# STM32-ROMI_Rev_A_4_3V_5V.net
KiCad netlist of a schematic drawn in Altium Designer
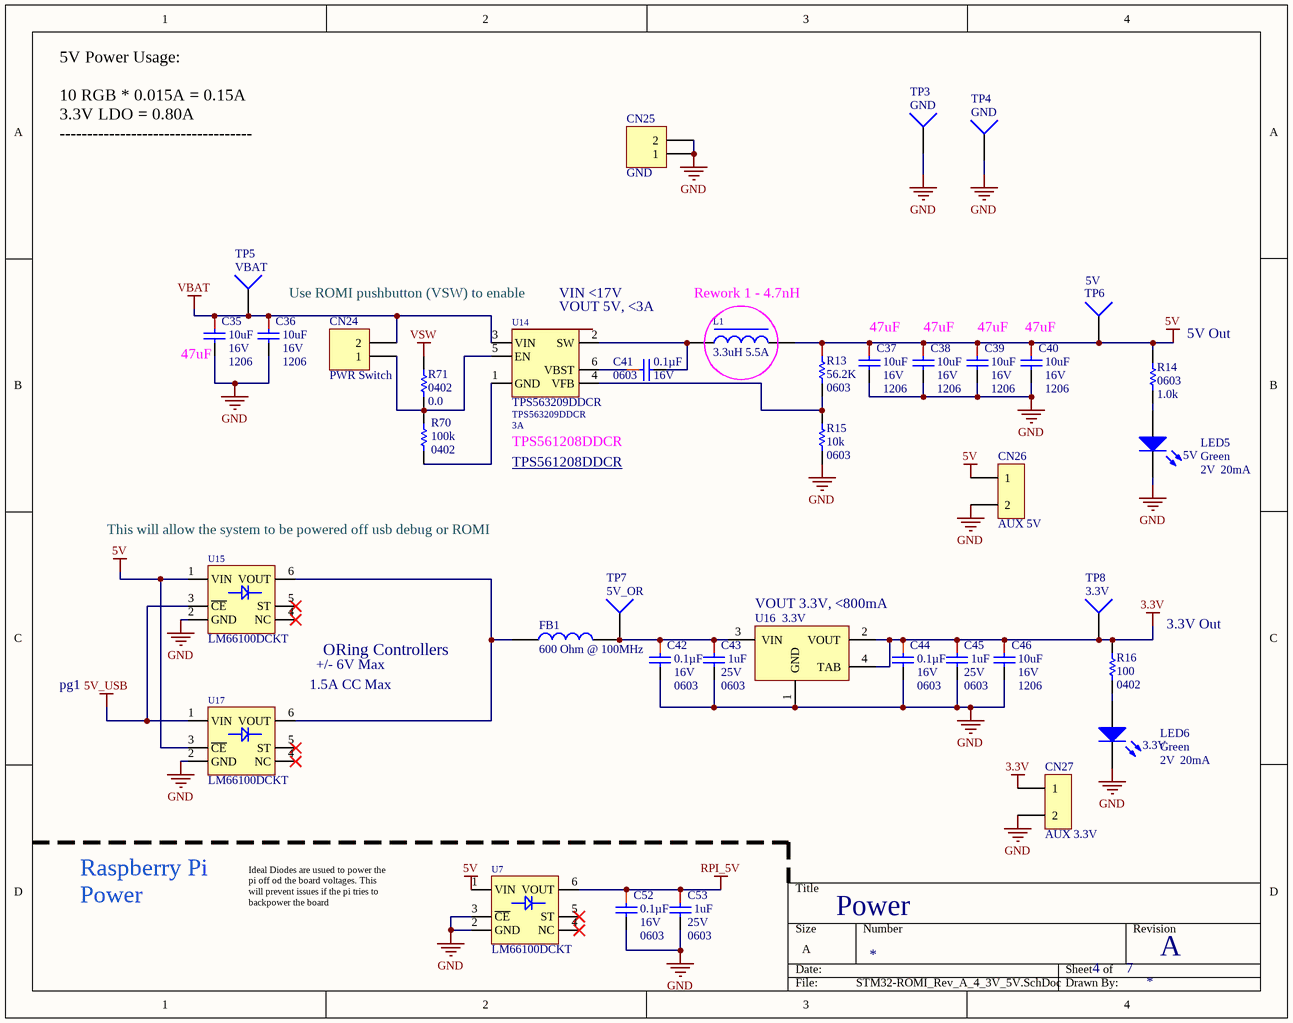
[diagram p0: STM32-ROMI_Rev_A_4_3V_5V.SchDoc]

(export (version "E")
  (design (tool "Eeschema 10.0.6"))
  (components
    (comp (ref "C35")
      (value "10uF")
      (footprint "CAPC1206(3216)_M")
      (fields (field (name "VOLTAGE - RATED") "16V") (field (name "PACKAGE") "1206"))
      (libsource (lib "Kyle-Passive") (part "CAP CER 10UF 16V 1206"))
    )
    (comp (ref "C36")
      (value "10uF")
      (footprint "CAPC1206(3216)_M")
      (fields (field (name "VOLTAGE - RATED") "16V") (field (name "PACKAGE") "1206"))
      (libsource (lib "Kyle-Passive") (part "CAP CER 10UF 16V 1206"))
    )
    (comp (ref "C37")
      (value "10uF")
      (footprint "CAPC1206(3216)_M")
      (fields (field (name "VOLTAGE - RATED") "16V") (field (name "PACKAGE") "1206"))
      (libsource (lib "Kyle-Passive") (part "CAP CER 10UF 16V 1206"))
    )
    (comp (ref "C38")
      (value "10uF")
      (footprint "CAPC1206(3216)_M")
      (fields (field (name "VOLTAGE - RATED") "16V") (field (name "PACKAGE") "1206"))
      (libsource (lib "Kyle-Passive") (part "CAP CER 10UF 16V 1206"))
    )
    (comp (ref "C39")
      (value "10uF")
      (footprint "CAPC1206(3216)_M")
      (fields (field (name "VOLTAGE - RATED") "16V") (field (name "PACKAGE") "1206"))
      (libsource (lib "Kyle-Passive") (part "CAP CER 10UF 16V 1206"))
    )
    (comp (ref "C40")
      (value "10uF")
      (footprint "CAPC1206(3216)_M")
      (fields (field (name "VOLTAGE - RATED") "16V") (field (name "PACKAGE") "1206"))
      (libsource (lib "Kyle-Passive") (part "CAP CER 10UF 16V 1206"))
    )
    (comp (ref "C41")
      (value "0.1uF")
      (footprint "CAPC0603(1608)_L")
      (description "0.1uF 0603 16V")
      (fields
        (field (name "MANUFACTURER") "Kemet")
        (field (name "MANUFACTURER PART NUMBER") "C0603C104K4RACTU")
        (field (name "CAPACITANCE") "0.1µF")
        (field (name "PACKAGE / CASE") "0603")
        (field (name "VOLTAGE - RATED") "16V")
      )
      (libsource (lib "Kyle-Passive") (part "CAP CER 0.1UF 16V 10% X7R 0603"))
    )
    (comp (ref "C42")
      (value "0.1uF")
      (footprint "CAPC0603(1608)_L")
      (description "0.1uF 0603 16V")
      (fields
        (field (name "MANUFACTURER") "Kemet")
        (field (name "MANUFACTURER PART NUMBER") "C0603C104K4RACTU")
        (field (name "CAPACITANCE") "0.1µF")
        (field (name "PACKAGE / CASE") "0603")
        (field (name "VOLTAGE - RATED") "16V")
      )
      (libsource (lib "Kyle-Passive") (part "CAP CER 0.1UF 16V 10% X7R 0603"))
    )
    (comp (ref "C43")
      (value "1uF")
      (footprint "CAPC0603(1608)_N")
      (description "1uF 0603 25V")
      (fields
        (field (name "MANUFACTURER") "TDK Corporation")
        (field (name "MANUFACTURER PART NUMBER") "CGA3E1X7R1E105K080AC")
        (field (name "VOLTAGE - RATED") "25V")
        (field (name "PACKAGE / CASE") "0603")
      )
      (libsource (lib "OLogic-Passive") (part "CAP CER 1UF 25V 10% X7R 0603"))
    )
    (comp (ref "C44")
      (value "0.1uF")
      (footprint "CAPC0603(1608)_L")
      (description "0.1uF 0603 16V")
      (fields
        (field (name "MANUFACTURER") "Kemet")
        (field (name "MANUFACTURER PART NUMBER") "C0603C104K4RACTU")
        (field (name "CAPACITANCE") "0.1µF")
        (field (name "PACKAGE / CASE") "0603")
        (field (name "VOLTAGE - RATED") "16V")
      )
      (libsource (lib "Kyle-Passive") (part "CAP CER 0.1UF 16V 10% X7R 0603"))
    )
    (comp (ref "C45")
      (value "1uF")
      (footprint "CAPC0603(1608)_N")
      (description "1uF 0603 25V")
      (fields
        (field (name "MANUFACTURER") "TDK Corporation")
        (field (name "MANUFACTURER PART NUMBER") "CGA3E1X7R1E105K080AC")
        (field (name "VOLTAGE - RATED") "25V")
        (field (name "PACKAGE / CASE") "0603")
      )
      (libsource (lib "OLogic-Passive") (part "CAP CER 1UF 25V 10% X7R 0603"))
    )
    (comp (ref "C46")
      (value "10uF")
      (footprint "CAPC1206(3216)_M")
      (fields (field (name "VOLTAGE - RATED") "16V") (field (name "PACKAGE") "1206"))
      (libsource (lib "Kyle-Passive") (part "CAP CER 10UF 16V 1206"))
    )
    (comp (ref "C52")
      (value "0.1uF")
      (footprint "CAPC0603(1608)_L")
      (description "0.1uF 0603 16V")
      (fields
        (field (name "MANUFACTURER") "Kemet")
        (field (name "MANUFACTURER PART NUMBER") "C0603C104K4RACTU")
        (field (name "CAPACITANCE") "0.1µF")
        (field (name "PACKAGE / CASE") "0603")
        (field (name "VOLTAGE - RATED") "16V")
      )
      (libsource (lib "Kyle-Passive") (part "CAP CER 0.1UF 16V 10% X7R 0603"))
    )
    (comp (ref "C53")
      (value "1uF")
      (footprint "CAPC0603(1608)_N")
      (description "1uF 0603 25V")
      (fields
        (field (name "MANUFACTURER") "TDK Corporation")
        (field (name "MANUFACTURER PART NUMBER") "CGA3E1X7R1E105K080AC")
        (field (name "VOLTAGE - RATED") "25V")
        (field (name "PACKAGE / CASE") "0603")
      )
      (libsource (lib "OLogic-Passive") (part "CAP CER 1UF 25V 10% X7R 0603"))
    )
    (comp (ref "CN24")
      (value "PWR Switch")
      (footprint "HDR1X2")
      (description "Header, 2-Pin")
      (fields
        (field (name "MANUFACTURER") "Sullins Connector Solutions")
        (field (name "MANUFACTURER PART NUMBER") "PRPC002SAAN-RC")
      )
      (libsource (lib "OLogic-Connectors") (part "Header 2"))
    )
    (comp (ref "CN25")
      (value "GND")
      (footprint "HDR1X2")
      (description "Header, 2-Pin")
      (fields
        (field (name "MANUFACTURER") "Sullins Connector Solutions")
        (field (name "MANUFACTURER PART NUMBER") "PRPC002SAAN-RC")
      )
      (libsource (lib "OLogic-Connectors") (part "Header 2"))
    )
    (comp (ref "CN26")
      (value "AUX 5V")
      (footprint "Molex 1x2 Microfit 3.0")
      (description "Molex Microfit 1x2 Vert Header")
      (fields
        (field (name "MANUFACTURER") "Molex, LLC")
        (field (name "MANUFACTURER PART NUMBER") "0430450227")
      )
      (libsource (lib "OLogic-Connectors") (part "MICROFIT 3.0 HDR VERT CPI 2CKT"))
    )
    (comp (ref "CN27")
      (value "AUX 3.3V")
      (footprint "Molex 1x2 Microfit 3.0")
      (description "Molex Microfit 1x2 Vert Header")
      (fields
        (field (name "MANUFACTURER") "Molex, LLC")
        (field (name "MANUFACTURER PART NUMBER") "0430450227")
      )
      (libsource (lib "OLogic-Connectors") (part "MICROFIT 3.0 HDR VERT CPI 2CKT"))
    )
    (comp (ref "FB1")
      (value "600 Ohm @ 100MHz")
      (footprint "RESC0805(2012)_N")
      (description "600 OHM 0805 2.0A")
      (fields
        (field (name "MANUFACTURER") "Wurth Electronics Inc")
        (field (name "MANUFACTURER PART NUMBER") "742792040")
        (field (name "CREATOR") "osman")
      )
      (libsource (lib "OLogic-Passive") (part "FERRITE 600 OHM 2.0A 0805"))
    )
    (comp (ref "L1")
      (value "3.3uH 5.5A")
      (footprint "YSPI0530-3R3M")
      (description "Power Inductors 3.3uH ±20% 5.5A SMD,5.2x4.7x3mm RoHS")
      (fields (field (name "MANUFACTURER PART") "YSPI0530-3R3M"))
      (libsource (lib "Kyle-Passive") (part "FIXED IND 3.3UH 5.5A 28 MOHM SMD"))
    )
    (comp (ref "LED5")
      (value "5V")
      (footprint "SM-LED-0603")
      (description "LED GREEN CLEAR THIN 0603 SMD")
      (fields
        (field (name "MANUFACTURER") "Lite-On Inc")
        (field (name "MANUFACTURER PART NUMBER") "LTST-C191KGKT")
        (field (name "COLOR") "Green")
        (field (name "VOLTAGE - FORWARD (VF) (TYP)") "2V")
        (field (name "CURRENT - TEST") "20mA")
      )
      (libsource (lib "Kyle-Diode-Opto-LED") (part "LTST-C191KGKT"))
    )
    (comp (ref "LED6")
      (value "3.3V")
      (footprint "SM-LED-0603")
      (description "LED GREEN CLEAR THIN 0603 SMD")
      (fields
        (field (name "MANUFACTURER") "Lite-On Inc")
        (field (name "MANUFACTURER PART NUMBER") "LTST-C191KGKT")
        (field (name "COLOR") "Green")
        (field (name "VOLTAGE - FORWARD (VF) (TYP)") "2V")
        (field (name "CURRENT - TEST") "20mA")
      )
      (libsource (lib "Kyle-Diode-Opto-LED") (part "LTST-C191KGKT"))
    )
    (comp (ref "R13")
      (value "56.2K")
      (footprint "RESC0603(1608)_L")
      (description "RES SMD 56.2K OHM 1% 1/10W 0603")
      (fields (field (name "PACKAGE / CASE") "0603"))
      (libsource (lib "Kyle-Passive") (part "RES SMD 56.2K OHM 1% 1/10W 0603"))
    )
    (comp (ref "R14")
      (value "1.0K")
      (footprint "RESC0603(1608)_N")
      (description "1.0K 0603")
      (fields
        (field (name "MANUFACTURER") "Stackpole Electronics Inc.")
        (field (name "MANUFACTURER PART NUMBER") "RMCF0603FT1K00")
        (field (name "PACKAGE / CASE") "0603")
        (field (name "RESISTANCE (OHMS)") "1.0k")
      )
      (libsource (lib "Kyle-Passive") (part "RES 1K OHM 1% 1/10W 0603"))
    )
    (comp (ref "R15")
      (value "10K 1%")
      (footprint "RESC0603(1608)_L")
      (description "10K 0603")
      (fields
        (field (name "MANUFACTURER") "Panasonic Electronic Components")
        (field (name "MANUFACTURER PART NUMBER") "ERJ-3EKF1002V")
        (field (name "RESISTANCE (OHMS)") "10k")
        (field (name "PACKAGE / CASE") "0603")
      )
      (libsource (lib "Kyle-Passive") (part "RES 10K OHM 1/10W 1% 0603 SMD"))
    )
    (comp (ref "R16")
      (value "100")
      (footprint "RESC0402(1005)_N")
      (description "100 0402")
      (fields
        (field (name "MANUFACTURER") "Yageo")
        (field (name "MANUFACTURER PART NUMBER") "RC0402FR-07100RL")
        (field (name "SUPPLIER DEVICE PACKAGE") "0402")
      )
      (libsource (lib "OLogic-Passive") (part "RES 100 OHM 1% 1/16W 0402"))
    )
    (comp (ref "R70")
      (value "100K 0402")
      (footprint "RESC0402(1005)_L")
      (fields
        (field (name "MANUFACTURER") "Yageo")
        (field (name "MANUFACTURER PART NUMBER") "RC0402FR-07100KL")
        (field (name "TOLERANCE") "±1%")
        (field (name "SUPPLIER DEVICE PACKAGE") "0402")
        (field (name "RESISTANCE (OHMS)") "100k")
      )
      (libsource (lib "OLogic-Passive") (part "RES 100K OHM 1% 1/16W 0402"))
    )
    (comp (ref "R71")
      (value "0")
      (footprint "RESC0402(1005)_L")
      (description "0.0 0402")
      (fields
        (field (name "MANUFACTURER") "Panasonic Electronic Components")
        (field (name "MANUFACTURER PART NUMBER") "ERJ-2GE0R00X")
        (field (name "SUPPLIER DEVICE PACKAGE") "0402")
        (field (name "RESISTANCE (OHMS)") "0.0")
        (field (name "CREATOR") "osman")
      )
      (libsource (lib "OLogic-Passive") (part "RES 0.0 OHM JUMPER 1/10W 0402"))
    )
    (comp (ref "TP3")
      (value "GND")
      (footprint "TestPoint-SM")
      (description "Test Point")
      (libsource (lib "OLogic-Misc") (part "TestPoint"))
    )
    (comp (ref "TP4")
      (value "GND")
      (footprint "TestPoint-SM")
      (description "Test Point")
      (libsource (lib "OLogic-Misc") (part "TestPoint"))
    )
    (comp (ref "TP5")
      (value "VBAT")
      (footprint "TestPoint-SM")
      (description "Test Point")
      (libsource (lib "OLogic-Misc") (part "TestPoint"))
    )
    (comp (ref "TP6")
      (value "5V")
      (footprint "TestPoint-SM")
      (description "Test Point")
      (libsource (lib "OLogic-Misc") (part "TestPoint"))
    )
    (comp (ref "TP7")
      (value "5V_OR")
      (footprint "TestPoint-SM")
      (description "Test Point")
      (libsource (lib "OLogic-Misc") (part "TestPoint"))
    )
    (comp (ref "TP8")
      (value "3.3V")
      (footprint "TestPoint-SM")
      (description "Test Point")
      (libsource (lib "OLogic-Misc") (part "TestPoint"))
    )
    (comp (ref "U7")
      (value "LM66100DCKT")
      (footprint "SC-70-6")
      (description "OR Controller P-Channel 1.5A CC")
      (libsource (lib "Kyle-Reg-Convert") (part "LM66100DCKT"))
    )
    (comp (ref "U14")
      (value "TPS563209DDCR")
      (footprint "SOT23-6")
      (description "IC REG BUCK ADJ 3A TSOT23-6")
      (fields
        (field (name "MANUFACTURER PART NUMBER") "TPS563209DDCR")
        (field (name "CURRENT - OUTPUT") "3A")
      )
      (libsource (lib "Kyle-Reg-Convert") (part "TPS563209DDCR"))
    )
    (comp (ref "U15")
      (value "LM66100DCKT")
      (footprint "SC-70-6")
      (description "OR Controller P-Channel 1.5A CC")
      (libsource (lib "Kyle-Reg-Convert") (part "LM66100DCKT"))
    )
    (comp (ref "U16")
      (value "3.3V")
      (footprint "DSO-G3")
      (description "3.3 volt fixed regulator, 800mA")
      (libsource (lib "OLogic-Reg-Convert") (part "LD1117S33"))
    )
    (comp (ref "U17")
      (value "LM66100DCKT")
      (footprint "SC-70-6")
      (description "OR Controller P-Channel 1.5A CC")
      (libsource (lib "Kyle-Reg-Convert") (part "LM66100DCKT"))
    )
  )
  (nets
    (net (code "1") (name "3.3V") (class "Default")
      (node (ref "C44") (pin "1") (pinfunction "1_1") (pintype "passive"))
      (node (ref "C45") (pin "1") (pinfunction "1_1") (pintype "passive"))
      (node (ref "C46") (pin "1") (pinfunction "1_1") (pintype "passive"))
      (node (ref "CN27") (pin "1") (pinfunction "1_1") (pintype "passive"))
      (node (ref "R16") (pin "2") (pinfunction "2_2") (pintype "passive"))
      (node (ref "TP8") (pin "1") (pinfunction "1_1") (pintype "passive"))
      (node (ref "U16") (pin "2") (pinfunction "VOUT_2") (pintype "power_in"))
      (node (ref "U16") (pin "4") (pinfunction "TAB_4") (pintype "power_in"))
    )
    (net (code "2") (name "5V") (class "Default")
      (node (ref "C37") (pin "1") (pinfunction "1_1") (pintype "passive"))
      (node (ref "C38") (pin "1") (pinfunction "1_1") (pintype "passive"))
      (node (ref "C39") (pin "1") (pinfunction "1_1") (pintype "passive"))
      (node (ref "C40") (pin "1") (pinfunction "1_1") (pintype "passive"))
      (node (ref "CN26") (pin "1") (pinfunction "1_1") (pintype "passive"))
      (node (ref "L1") (pin "2") (pinfunction "2_2") (pintype "passive"))
      (node (ref "R13") (pin "1") (pinfunction "1_1") (pintype "passive"))
      (node (ref "R14") (pin "2") (pinfunction "2_2") (pintype "passive"))
      (node (ref "TP6") (pin "1") (pinfunction "1_1") (pintype "passive"))
      (node (ref "U15") (pin "1") (pinfunction "VIN_1") (pintype "passive"))
      (node (ref "U17") (pin "3") (pinfunction "~{CE}_3") (pintype "passive"))
      (node (ref "U7") (pin "1") (pinfunction "VIN_1") (pintype "passive"))
    )
    (net (code "3") (name "5V_USB") (class "Default")
      (node (ref "U15") (pin "3") (pinfunction "~{CE}_3") (pintype "passive"))
      (node (ref "U17") (pin "1") (pinfunction "VIN_1") (pintype "passive"))
    )
    (net (code "4") (name "GND") (class "Default")
      (node (ref "C35") (pin "2") (pinfunction "2_2") (pintype "passive"))
      (node (ref "C36") (pin "2") (pinfunction "2_2") (pintype "passive"))
      (node (ref "C37") (pin "2") (pinfunction "2_2") (pintype "passive"))
      (node (ref "C38") (pin "2") (pinfunction "2_2") (pintype "passive"))
      (node (ref "C39") (pin "2") (pinfunction "2_2") (pintype "passive"))
      (node (ref "C40") (pin "2") (pinfunction "2_2") (pintype "passive"))
      (node (ref "C42") (pin "2") (pinfunction "2_2") (pintype "passive"))
      (node (ref "C43") (pin "2") (pinfunction "2_2") (pintype "passive"))
      (node (ref "C44") (pin "2") (pinfunction "2_2") (pintype "passive"))
      (node (ref "C45") (pin "2") (pinfunction "2_2") (pintype "passive"))
      (node (ref "C46") (pin "2") (pinfunction "2_2") (pintype "passive"))
      (node (ref "C52") (pin "2") (pinfunction "2_2") (pintype "passive"))
      (node (ref "C53") (pin "2") (pinfunction "2_2") (pintype "passive"))
      (node (ref "CN25") (pin "1") (pinfunction "1_1") (pintype "passive"))
      (node (ref "CN25") (pin "2") (pinfunction "2_2") (pintype "passive"))
      (node (ref "CN26") (pin "2") (pinfunction "2_2") (pintype "passive"))
      (node (ref "CN27") (pin "2") (pinfunction "2_2") (pintype "passive"))
      (node (ref "LED5") (pin "2") (pinfunction "2_2") (pintype "passive"))
      (node (ref "LED6") (pin "2") (pinfunction "2_2") (pintype "passive"))
      (node (ref "R15") (pin "1") (pinfunction "1_1") (pintype "passive"))
      (node (ref "TP3") (pin "1") (pinfunction "1_1") (pintype "passive"))
      (node (ref "TP4") (pin "1") (pinfunction "1_1") (pintype "passive"))
      (node (ref "U15") (pin "2") (pinfunction "GND_2") (pintype "passive"))
      (node (ref "U16") (pin "1") (pinfunction "GND_1") (pintype "power_in"))
      (node (ref "U17") (pin "2") (pinfunction "GND_2") (pintype "passive"))
      (node (ref "U7") (pin "2") (pinfunction "GND_2") (pintype "passive"))
      (node (ref "U7") (pin "3") (pinfunction "~{CE}_3") (pintype "passive"))
    )
    (net (code "5") (name "Net-(LED5-Pad1)") (class "Default")
      (node (ref "LED5") (pin "1") (pinfunction "1_1") (pintype "passive"))
      (node (ref "R14") (pin "1") (pinfunction "1_1") (pintype "passive"))
    )
    (net (code "6") (name "Net-(LED6-Pad1)") (class "Default")
      (node (ref "LED6") (pin "1") (pinfunction "1_1") (pintype "passive"))
      (node (ref "R16") (pin "1") (pinfunction "1_1") (pintype "passive"))
    )
    (net (code "7") (name "Net-(U14-EN)") (class "Default")
      (node (ref "CN24") (pin "1") (pinfunction "1_1") (pintype "passive"))
      (node (ref "R70") (pin "2") (pinfunction "2_2") (pintype "passive"))
      (node (ref "R71") (pin "2") (pinfunction "2_2") (pintype "passive"))
      (node (ref "U14") (pin "5") (pinfunction "EN_5") (pintype "power_in"))
    )
    (net (code "8") (name "Net-(U14-GND)") (class "Default")
      (node (ref "R70") (pin "1") (pinfunction "1_1") (pintype "passive"))
      (node (ref "U14") (pin "1") (pinfunction "GND_1") (pintype "power_in"))
    )
    (net (code "9") (name "Net-(U14-SW)") (class "Default")
      (node (ref "C41") (pin "2") (pinfunction "2_2") (pintype "passive"))
      (node (ref "L1") (pin "1") (pinfunction "1_1") (pintype "passive"))
      (node (ref "U14") (pin "2") (pinfunction "SW_2") (pintype "power_in"))
    )
    (net (code "10") (name "Net-(U14-VBST)") (class "Default")
      (node (ref "C41") (pin "1") (pinfunction "1_1") (pintype "passive"))
      (node (ref "U14") (pin "6") (pinfunction "VBST_6") (pintype "power_in"))
    )
    (net (code "11") (name "Net-(U14-VFB)") (class "Default")
      (node (ref "R13") (pin "2") (pinfunction "2_2") (pintype "passive"))
      (node (ref "R15") (pin "2") (pinfunction "2_2") (pintype "passive"))
      (node (ref "U14") (pin "4") (pinfunction "VFB_4") (pintype "power_in"))
    )
    (net (code "12") (name "Net-(U15-VOUT)") (class "Default")
      (node (ref "FB1") (pin "1") (pinfunction "1_1") (pintype "passive"))
      (node (ref "U15") (pin "6") (pinfunction "VOUT_6") (pintype "passive"))
      (node (ref "U17") (pin "6") (pinfunction "VOUT_6") (pintype "passive"))
    )
    (net (code "13") (name "Net-(U16-VIN)") (class "Default")
      (node (ref "C42") (pin "1") (pinfunction "1_1") (pintype "passive"))
      (node (ref "C43") (pin "1") (pinfunction "1_1") (pintype "passive"))
      (node (ref "FB1") (pin "2") (pinfunction "2_2") (pintype "passive"))
      (node (ref "TP7") (pin "1") (pinfunction "1_1") (pintype "passive"))
      (node (ref "U16") (pin "3") (pinfunction "VIN_3") (pintype "power_in"))
    )
    (net (code "14") (name "RPI_5V") (class "Default")
      (node (ref "C52") (pin "1") (pinfunction "1_1") (pintype "passive"))
      (node (ref "C53") (pin "1") (pinfunction "1_1") (pintype "passive"))
      (node (ref "U7") (pin "6") (pinfunction "VOUT_6") (pintype "passive"))
    )
    (net (code "15") (name "VBAT") (class "Default")
      (node (ref "C35") (pin "1") (pinfunction "1_1") (pintype "passive"))
      (node (ref "C36") (pin "1") (pinfunction "1_1") (pintype "passive"))
      (node (ref "CN24") (pin "2") (pinfunction "2_2") (pintype "passive"))
      (node (ref "TP5") (pin "1") (pinfunction "1_1") (pintype "passive"))
      (node (ref "U14") (pin "3") (pinfunction "VIN_3") (pintype "power_in"))
    )
    (net (code "16") (name "VSW") (class "Default")
      (node (ref "R71") (pin "1") (pinfunction "1_1") (pintype "passive"))
    )
    (net (code "17") (name "unconnected-(U7-NC-Pad4)") (class "Default")
      (node (ref "U7") (pin "4") (pinfunction "NC_4") (pintype "passive+no_connect"))
    )
    (net (code "18") (name "unconnected-(U7-ST-Pad5)") (class "Default")
      (node (ref "U7") (pin "5") (pinfunction "ST_5") (pintype "passive+no_connect"))
    )
    (net (code "19") (name "unconnected-(U15-NC-Pad4)") (class "Default")
      (node (ref "U15") (pin "4") (pinfunction "NC_4") (pintype "passive+no_connect"))
    )
    (net (code "20") (name "unconnected-(U15-ST-Pad5)") (class "Default")
      (node (ref "U15") (pin "5") (pinfunction "ST_5") (pintype "passive+no_connect"))
    )
    (net (code "21") (name "unconnected-(U17-NC-Pad4)") (class "Default")
      (node (ref "U17") (pin "4") (pinfunction "NC_4") (pintype "passive+no_connect"))
    )
    (net (code "22") (name "unconnected-(U17-ST-Pad5)") (class "Default")
      (node (ref "U17") (pin "5") (pinfunction "ST_5") (pintype "passive+no_connect"))
    )
  )
)
